# coilcube.net
KiCad netlist of a schematic drawn in EAGLE
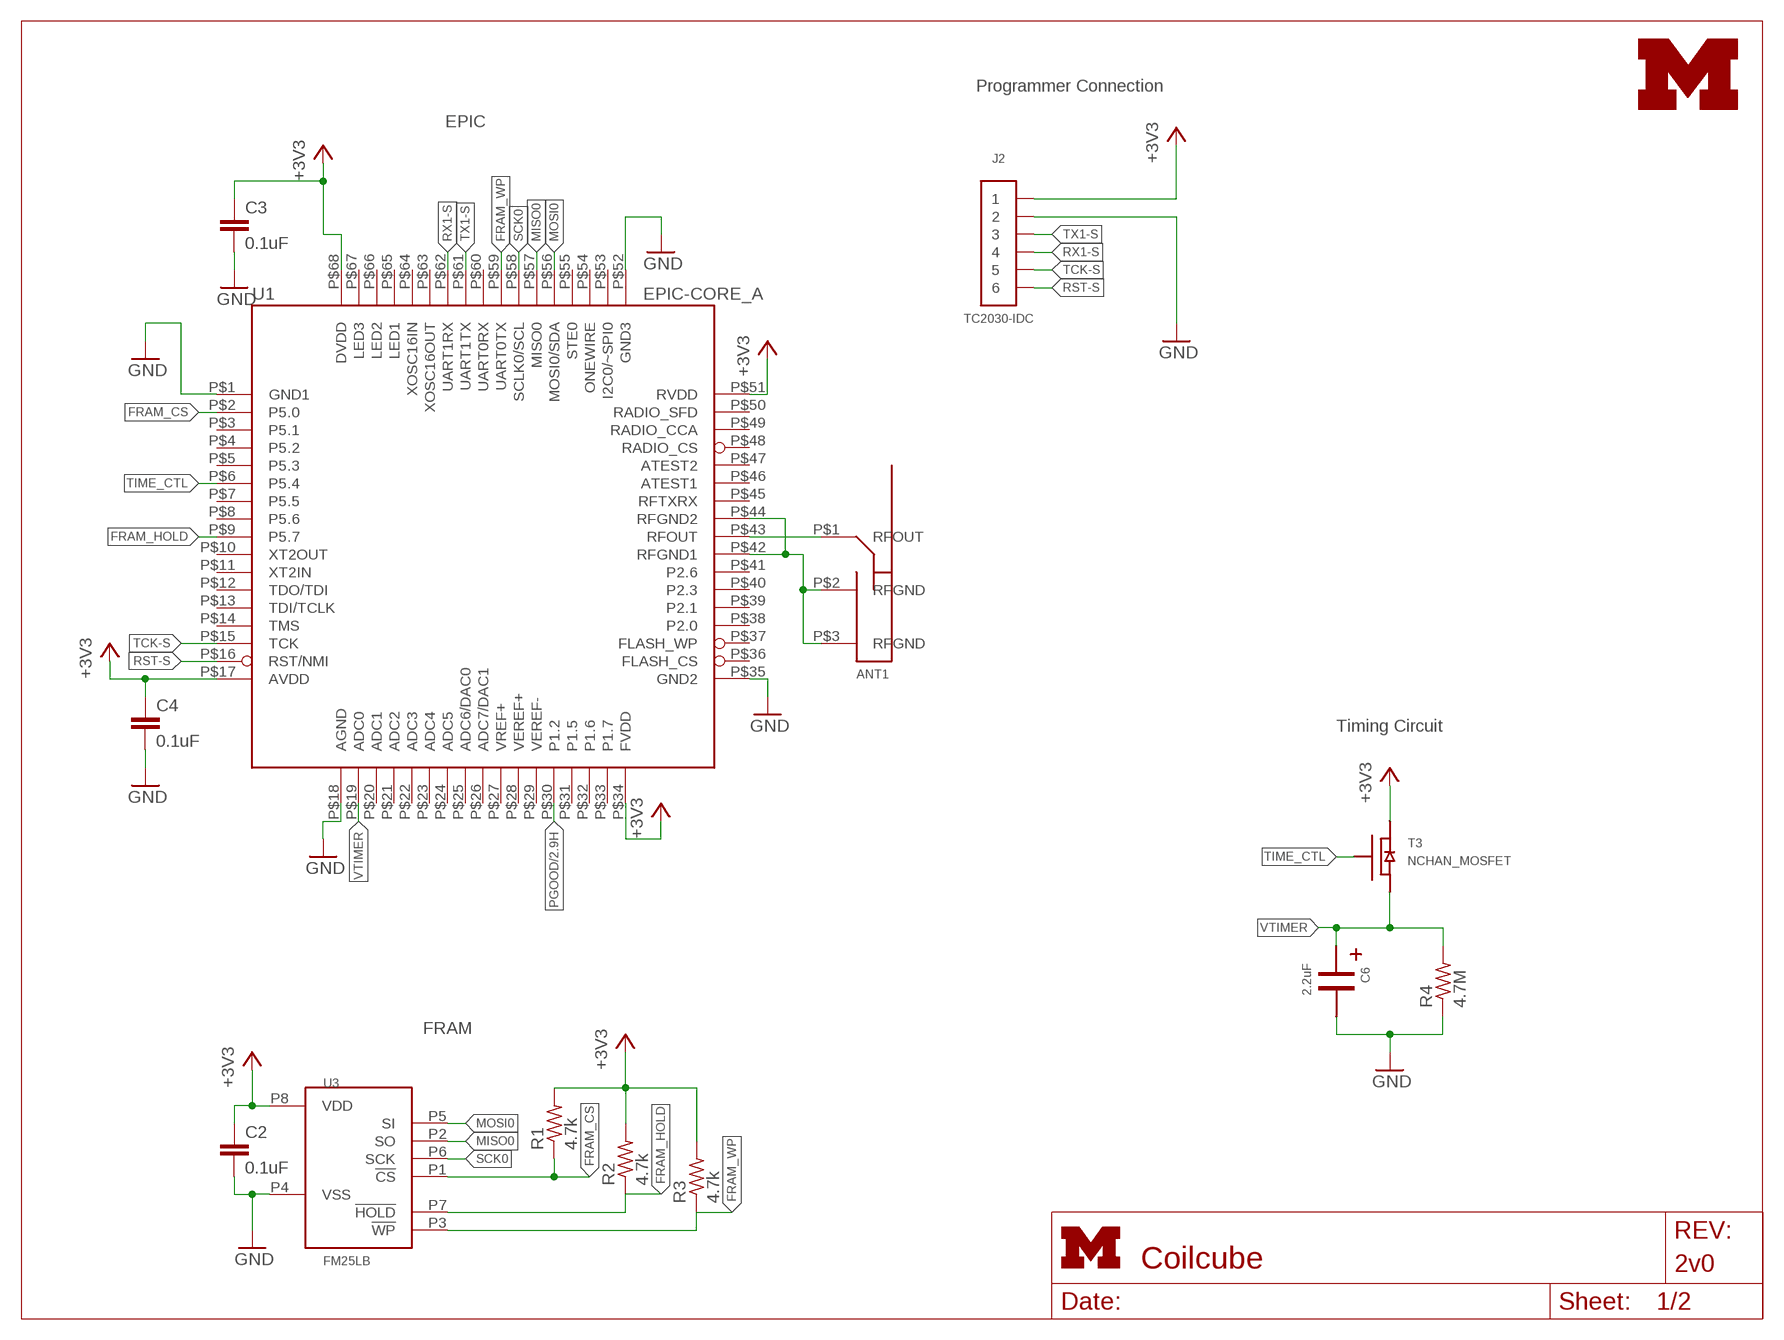
[diagram p0: schematic, sheet 1]
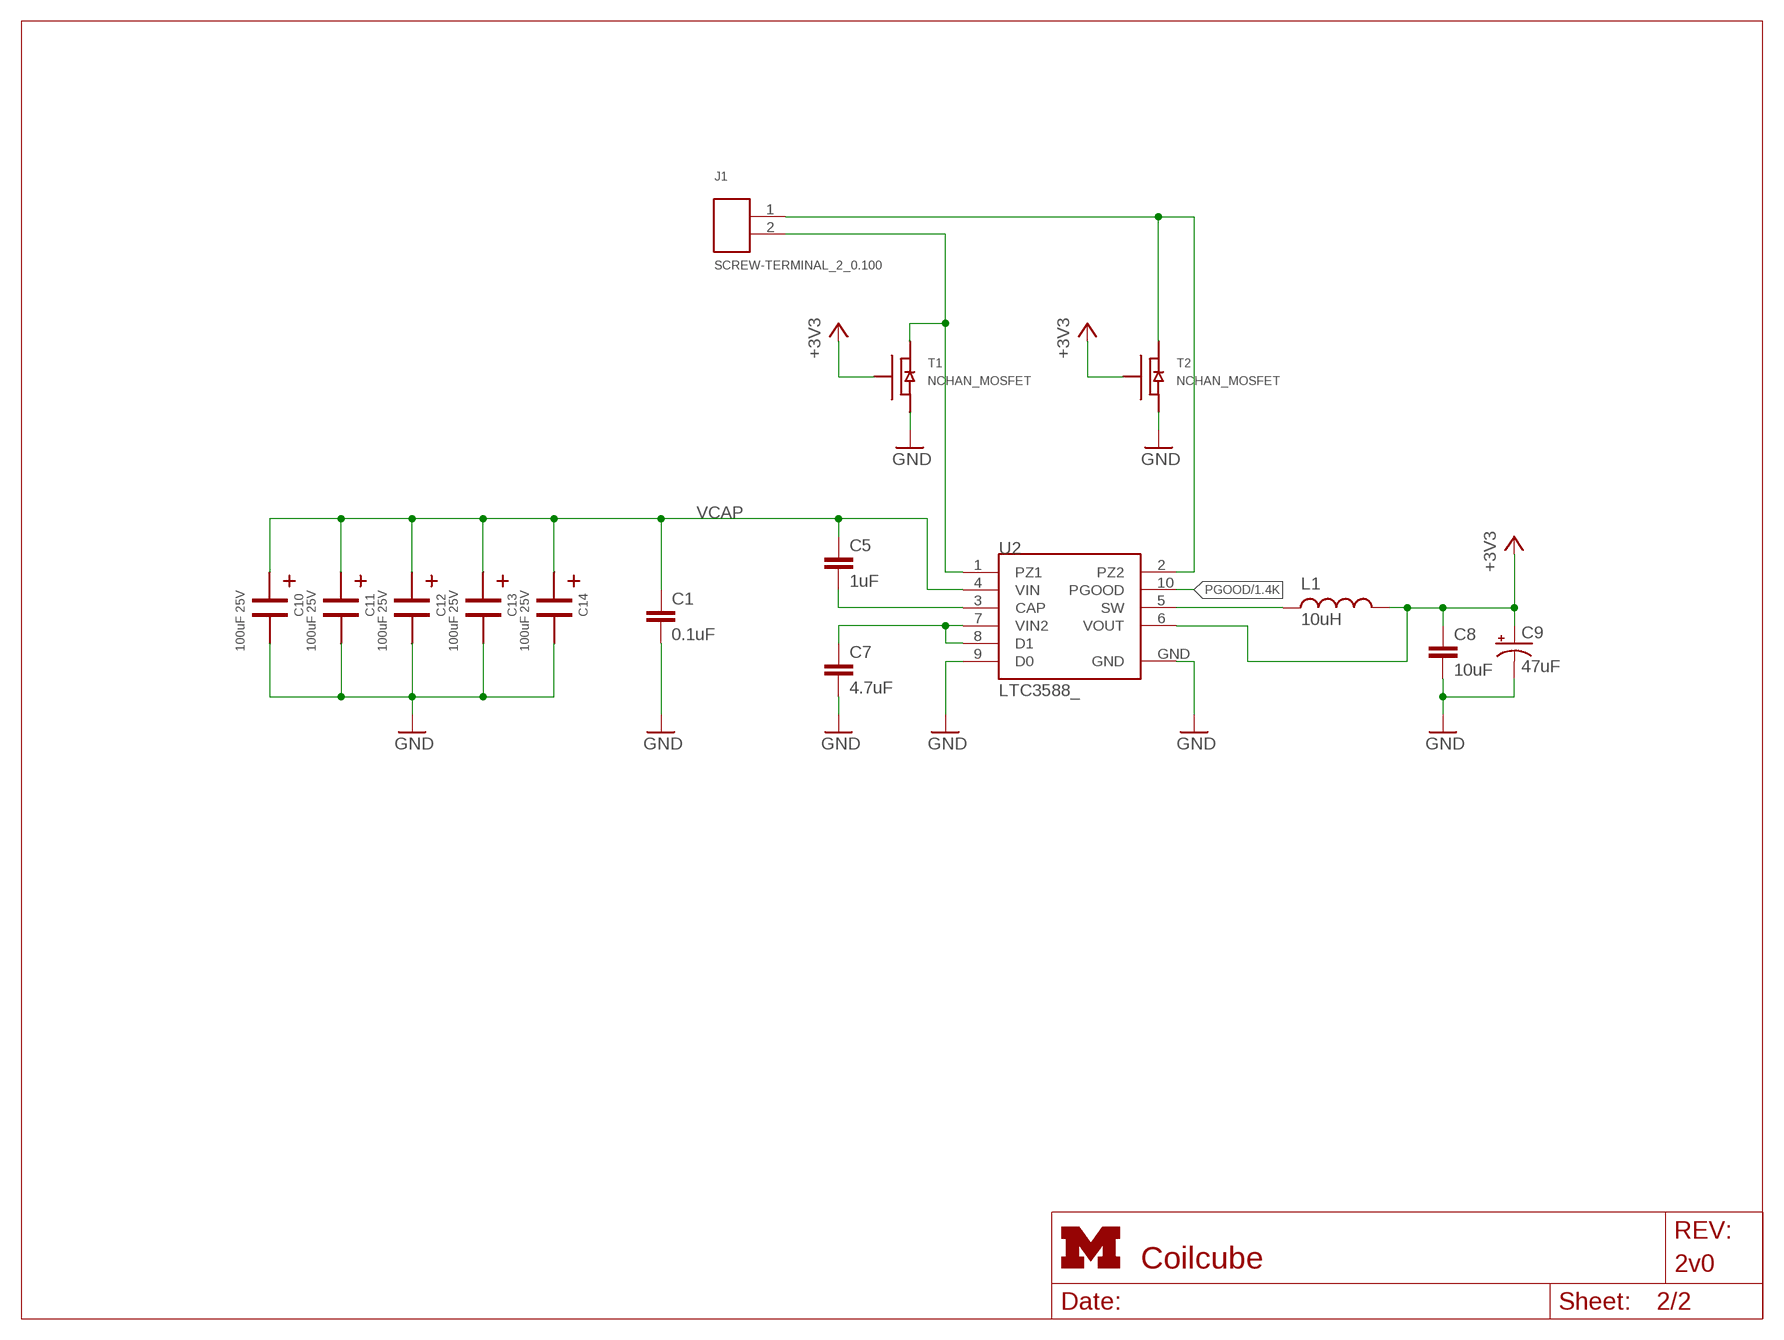
[diagram p1: schematic, sheet 2]

(export (version "E")
  (design (tool "Eeschema 10.0.6"))
  (components
    (comp (ref "ANT1")
      (value "PIFA-2.4GHZ")
      (footprint "eagle-import:PIFA-2.4GHZ")
      (libsource (lib "eagle-import") (part "PIFA-2.4GHZ"))
    )
    (comp (ref "C2")
      (value "0.1uF")
      (footprint "eagle-import:C0603")
      (libsource (lib "eagle-import") (part "C-EUC0603"))
    )
    (comp (ref "C3")
      (value "0.1uF")
      (footprint "eagle-import:C0603")
      (libsource (lib "eagle-import") (part "C-EUC0603"))
    )
    (comp (ref "C4")
      (value "0.1uF")
      (footprint "eagle-import:C0603")
      (libsource (lib "eagle-import") (part "C-EUC0603"))
    )
    (comp (ref "C6")
      (value "2.2uF")
      (footprint "eagle-import:CPOL_EEA_1MM5")
      (libsource (lib "eagle-import") (part "CAP_POLEA1MM5"))
    )
    (comp (ref "J2")
      (value "TC2030-IDC")
      (footprint "eagle-import:TC2030-IDC")
      (libsource (lib "eagle-import") (part "TC2030-IDC"))
    )
    (comp (ref "R1")
      (value "4.7k")
      (footprint "eagle-import:R0603")
      (libsource (lib "eagle-import") (part "R-US_R0603"))
    )
    (comp (ref "R2")
      (value "4.7k")
      (footprint "eagle-import:R0603")
      (libsource (lib "eagle-import") (part "R-US_R0603"))
    )
    (comp (ref "R3")
      (value "4.7k")
      (footprint "eagle-import:R0603")
      (libsource (lib "eagle-import") (part "R-US_R0603"))
    )
    (comp (ref "R4")
      (value "4.7M")
      (footprint "eagle-import:R0805")
      (libsource (lib "eagle-import") (part "R-US_R0805"))
    )
    (comp (ref "T3")
      (value "NCHAN_MOSFET")
      (footprint "eagle-import:NCHAN_MOSFET")
      (libsource (lib "eagle-import") (part "NCHAN_MOSFET"))
    )
    (comp (ref "U$1")
      (value "UMICH_SOLID_MEDIUM")
      (footprint "eagle-import:UMICH_SOLID_200MIL")
      (libsource (lib "eagle-import") (part "UMICH_SOLID_MEDIUM"))
    )
    (comp (ref "U1")
      (value "EPIC-CORE_A")
      (footprint "eagle-import:EPIC-LCC68")
      (libsource (lib "eagle-import") (part "EPIC-CORE_A"))
    )
    (comp (ref "U3")
      (value "FM25LB")
      (footprint "eagle-import:SOIC_8")
      (libsource (lib "eagle-import") (part "FM25LB"))
    )
    (comp (ref "C1")
      (value "0.1uF")
      (footprint "eagle-import:C0603")
      (libsource (lib "eagle-import") (part "C-EUC0603"))
    )
    (comp (ref "C5")
      (value "1uF")
      (footprint "eagle-import:C0603")
      (libsource (lib "eagle-import") (part "C-EUC0603"))
    )
    (comp (ref "C7")
      (value "4.7uF")
      (footprint "eagle-import:C0603")
      (libsource (lib "eagle-import") (part "C-EUC0603"))
    )
    (comp (ref "C8")
      (value "10uF")
      (footprint "eagle-import:C1206")
      (libsource (lib "eagle-import") (part "C-EUC1206"))
    )
    (comp (ref "C9")
      (value "47uF")
      (footprint "eagle-import:EIA3216")
      (libsource (lib "eagle-import") (part "CAP_POL1206"))
    )
    (comp (ref "C10")
      (value "100uF 25V")
      (footprint "eagle-import:2917_CAP_POL")
      (libsource (lib "eagle-import") (part "2917_CAP_POL"))
    )
    (comp (ref "C11")
      (value "100uF 25V")
      (footprint "eagle-import:2917_CAP_POL")
      (libsource (lib "eagle-import") (part "2917_CAP_POL"))
    )
    (comp (ref "C12")
      (value "100uF 25V")
      (footprint "eagle-import:2917_CAP_POL")
      (libsource (lib "eagle-import") (part "2917_CAP_POL"))
    )
    (comp (ref "C13")
      (value "100uF 25V")
      (footprint "eagle-import:2917_CAP_POL")
      (libsource (lib "eagle-import") (part "2917_CAP_POL"))
    )
    (comp (ref "C14")
      (value "100uF 25V")
      (footprint "eagle-import:2917_CAP_POL")
      (libsource (lib "eagle-import") (part "2917_CAP_POL"))
    )
    (comp (ref "J1")
      (value "SCREW-TERMINAL_2_0.100")
      (footprint "eagle-import:CONN_BLOCK_2")
      (libsource (lib "eagle-import") (part "SCREW-TERMINAL_2_0.100"))
    )
    (comp (ref "L1")
      (value "10uH")
      (footprint "eagle-import:1210")
      (libsource (lib "eagle-import") (part "INDUCTOR1210"))
    )
    (comp (ref "T1")
      (value "NCHAN_MOSFET")
      (footprint "eagle-import:NCHAN_MOSFET")
      (libsource (lib "eagle-import") (part "NCHAN_MOSFET"))
    )
    (comp (ref "T2")
      (value "NCHAN_MOSFET")
      (footprint "eagle-import:NCHAN_MOSFET")
      (libsource (lib "eagle-import") (part "NCHAN_MOSFET"))
    )
    (comp (ref "U2")
      (value "LTC3588_")
      (footprint "eagle-import:MSOP-10-GNDPAD")
      (libsource (lib "eagle-import") (part "LTC3588_"))
    )
  )
  (nets
    (net (code "1") (name "+3V3") (class "Default")
      (node (ref "C2") (pin "1") (pinfunction "1_1") (pintype "passive"))
      (node (ref "C3") (pin "1") (pinfunction "1_1") (pintype "passive"))
      (node (ref "C4") (pin "1") (pinfunction "1_1") (pintype "passive"))
      (node (ref "C8") (pin "1") (pinfunction "1_1") (pintype "passive"))
      (node (ref "C9") (pin "A") (pinfunction "+_A") (pintype "passive"))
      (node (ref "J2") (pin "1") (pinfunction "1_1") (pintype "bidirectional"))
      (node (ref "L1") (pin "2") (pinfunction "2_2") (pintype "passive"))
      (node (ref "R1") (pin "2") (pinfunction "2_2") (pintype "passive"))
      (node (ref "R2") (pin "2") (pinfunction "2_2") (pintype "passive"))
      (node (ref "R3") (pin "2") (pinfunction "2_2") (pintype "passive"))
      (node (ref "T1") (pin "G") (pinfunction "G_G") (pintype "bidirectional"))
      (node (ref "T2") (pin "G") (pinfunction "G_G") (pintype "bidirectional"))
      (node (ref "T3") (pin "D") (pinfunction "D_D") (pintype "bidirectional"))
      (node (ref "U1") (pin "P$17") (pinfunction "AVDD_P$17") (pintype "bidirectional"))
      (node (ref "U1") (pin "P$34") (pinfunction "FVDD_P$34") (pintype "bidirectional"))
      (node (ref "U1") (pin "P$51") (pinfunction "RVDD_P$51") (pintype "bidirectional"))
      (node (ref "U1") (pin "P$68") (pinfunction "DVDD_P$68") (pintype "bidirectional"))
      (node (ref "U2") (pin "6") (pinfunction "VOUT_6") (pintype "bidirectional"))
      (node (ref "U3") (pin "P8") (pinfunction "VDD_P8") (pintype "bidirectional"))
    )
    (net (code "2") (name "FRAM_CS") (class "Default")
      (node (ref "R1") (pin "1") (pinfunction "1_1") (pintype "passive"))
      (node (ref "U1") (pin "P$2") (pinfunction "P5.0_P$2") (pintype "bidirectional"))
      (node (ref "U3") (pin "P1") (pinfunction "~{CS}_P1") (pintype "bidirectional"))
    )
    (net (code "3") (name "FRAM_HOLD") (class "Default")
      (node (ref "R2") (pin "1") (pinfunction "1_1") (pintype "passive"))
      (node (ref "U1") (pin "P$9") (pinfunction "P5.7_P$9") (pintype "bidirectional"))
      (node (ref "U3") (pin "P7") (pinfunction "~{HOLD}_P7") (pintype "bidirectional"))
    )
    (net (code "4") (name "FRAM_WP") (class "Default")
      (node (ref "R3") (pin "1") (pinfunction "1_1") (pintype "passive"))
      (node (ref "U1") (pin "P$59") (pinfunction "UART0TX_P$59") (pintype "bidirectional"))
      (node (ref "U3") (pin "P3") (pinfunction "~{WP}_P3") (pintype "bidirectional"))
    )
    (net (code "5") (name "GND") (class "Default")
      (node (ref "C1") (pin "2") (pinfunction "2_2") (pintype "passive"))
      (node (ref "C10") (pin "-") (pinfunction "-_-") (pintype "bidirectional"))
      (node (ref "C11") (pin "-") (pinfunction "-_-") (pintype "bidirectional"))
      (node (ref "C12") (pin "-") (pinfunction "-_-") (pintype "bidirectional"))
      (node (ref "C13") (pin "-") (pinfunction "-_-") (pintype "bidirectional"))
      (node (ref "C14") (pin "-") (pinfunction "-_-") (pintype "bidirectional"))
      (node (ref "C2") (pin "2") (pinfunction "2_2") (pintype "passive"))
      (node (ref "C3") (pin "2") (pinfunction "2_2") (pintype "passive"))
      (node (ref "C4") (pin "2") (pinfunction "2_2") (pintype "passive"))
      (node (ref "C6") (pin "-") (pinfunction "-_-") (pintype "bidirectional"))
      (node (ref "C7") (pin "2") (pinfunction "2_2") (pintype "passive"))
      (node (ref "C8") (pin "2") (pinfunction "2_2") (pintype "passive"))
      (node (ref "C9") (pin "C") (pinfunction "-_C") (pintype "passive"))
      (node (ref "J2") (pin "2") (pinfunction "2_2") (pintype "bidirectional"))
      (node (ref "R4") (pin "1") (pinfunction "1_1") (pintype "passive"))
      (node (ref "T1") (pin "S") (pinfunction "S_S") (pintype "bidirectional"))
      (node (ref "T2") (pin "S") (pinfunction "S_S") (pintype "bidirectional"))
      (node (ref "U1") (pin "P$1") (pinfunction "GND1_P$1") (pintype "bidirectional"))
      (node (ref "U1") (pin "P$18") (pinfunction "AGND_P$18") (pintype "bidirectional"))
      (node (ref "U1") (pin "P$35") (pinfunction "GND2_P$35") (pintype "bidirectional"))
      (node (ref "U1") (pin "P$52") (pinfunction "GND3_P$52") (pintype "bidirectional"))
      (node (ref "U2") (pin "9") (pinfunction "D0_9") (pintype "bidirectional"))
      (node (ref "U2") (pin "GND") (pinfunction "GND_GND") (pintype "bidirectional"))
      (node (ref "U3") (pin "P4") (pinfunction "VSS_P4") (pintype "bidirectional"))
    )
    (net (code "6") (name "MISO0") (class "Default")
      (node (ref "U1") (pin "P$57") (pinfunction "MISO0_P$57") (pintype "bidirectional"))
      (node (ref "U3") (pin "P2") (pinfunction "SO_P2") (pintype "bidirectional"))
    )
    (net (code "7") (name "MOSI0") (class "Default")
      (node (ref "U1") (pin "P$56") (pinfunction "MOSI0/SDA_P$56") (pintype "bidirectional"))
      (node (ref "U3") (pin "P5") (pinfunction "SI_P5") (pintype "bidirectional"))
    )
    (net (code "8") (name "Net-(ANT1-RFOUT)") (class "Default")
      (node (ref "ANT1") (pin "P$1") (pinfunction "RFOUT_P$1") (pintype "bidirectional"))
      (node (ref "U1") (pin "P$43") (pinfunction "RFOUT_P$43") (pintype "bidirectional"))
    )
    (net (code "9") (name "Net-(U1-RFGND1)") (class "Default")
      (node (ref "ANT1") (pin "P$2") (pinfunction "RFGND_P$2") (pintype "bidirectional"))
      (node (ref "ANT1") (pin "P$3") (pinfunction "RFGND_P$3") (pintype "bidirectional"))
      (node (ref "U1") (pin "P$42") (pinfunction "RFGND1_P$42") (pintype "bidirectional"))
      (node (ref "U1") (pin "P$44") (pinfunction "RFGND2_P$44") (pintype "bidirectional"))
    )
    (net (code "10") (name "Net-(U2-CAP)") (class "Default")
      (node (ref "C5") (pin "2") (pinfunction "2_2") (pintype "passive"))
      (node (ref "U2") (pin "3") (pinfunction "CAP_3") (pintype "bidirectional"))
    )
    (net (code "11") (name "Net-(U2-D1)") (class "Default")
      (node (ref "C7") (pin "1") (pinfunction "1_1") (pintype "passive"))
      (node (ref "U2") (pin "7") (pinfunction "VIN2_7") (pintype "bidirectional"))
      (node (ref "U2") (pin "8") (pinfunction "D1_8") (pintype "bidirectional"))
    )
    (net (code "12") (name "Net-(U2-PZ1)") (class "Default")
      (node (ref "J1") (pin "2") (pinfunction "2_2") (pintype "bidirectional"))
      (node (ref "T1") (pin "D") (pinfunction "D_D") (pintype "bidirectional"))
      (node (ref "U2") (pin "1") (pinfunction "PZ1_1") (pintype "bidirectional"))
    )
    (net (code "13") (name "Net-(U2-PZ2)") (class "Default")
      (node (ref "J1") (pin "1") (pinfunction "1_1") (pintype "bidirectional"))
      (node (ref "T2") (pin "D") (pinfunction "D_D") (pintype "bidirectional"))
      (node (ref "U2") (pin "2") (pinfunction "PZ2_2") (pintype "bidirectional"))
    )
    (net (code "14") (name "Net-(U2-SW)") (class "Default")
      (node (ref "L1") (pin "1") (pinfunction "1_1") (pintype "passive"))
      (node (ref "U2") (pin "5") (pinfunction "SW_5") (pintype "bidirectional"))
    )
    (net (code "15") (name "PGOOD") (class "Default")
      (node (ref "U1") (pin "P$30") (pinfunction "P1.2_P$30") (pintype "bidirectional"))
      (node (ref "U2") (pin "10") (pinfunction "PGOOD_10") (pintype "bidirectional"))
    )
    (net (code "16") (name "RST-S") (class "Default")
      (node (ref "J2") (pin "6") (pinfunction "6_6") (pintype "bidirectional"))
      (node (ref "U1") (pin "P$16") (pinfunction "RST/NMI_P$16") (pintype "bidirectional"))
    )
    (net (code "17") (name "RX1-S") (class "Default")
      (node (ref "J2") (pin "4") (pinfunction "4_4") (pintype "bidirectional"))
      (node (ref "U1") (pin "P$62") (pinfunction "UART1RX_P$62") (pintype "bidirectional"))
    )
    (net (code "18") (name "SCK0") (class "Default")
      (node (ref "U1") (pin "P$58") (pinfunction "SCLK0/SCL_P$58") (pintype "bidirectional"))
      (node (ref "U3") (pin "P6") (pinfunction "SCK_P6") (pintype "bidirectional"))
    )
    (net (code "19") (name "TCK-S") (class "Default")
      (node (ref "J2") (pin "5") (pinfunction "5_5") (pintype "bidirectional"))
      (node (ref "U1") (pin "P$15") (pinfunction "TCK_P$15") (pintype "bidirectional"))
    )
    (net (code "20") (name "TIME_CTL") (class "Default")
      (node (ref "T3") (pin "G") (pinfunction "G_G") (pintype "bidirectional"))
      (node (ref "U1") (pin "P$6") (pinfunction "P5.4_P$6") (pintype "bidirectional"))
    )
    (net (code "21") (name "TX1-S") (class "Default")
      (node (ref "J2") (pin "3") (pinfunction "3_3") (pintype "bidirectional"))
      (node (ref "U1") (pin "P$61") (pinfunction "UART1TX_P$61") (pintype "bidirectional"))
    )
    (net (code "22") (name "VCAP") (class "Default")
      (node (ref "C1") (pin "1") (pinfunction "1_1") (pintype "passive"))
      (node (ref "C10") (pin "+") (pinfunction "+_+") (pintype "bidirectional"))
      (node (ref "C11") (pin "+") (pinfunction "+_+") (pintype "bidirectional"))
      (node (ref "C12") (pin "+") (pinfunction "+_+") (pintype "bidirectional"))
      (node (ref "C13") (pin "+") (pinfunction "+_+") (pintype "bidirectional"))
      (node (ref "C14") (pin "+") (pinfunction "+_+") (pintype "bidirectional"))
      (node (ref "C5") (pin "1") (pinfunction "1_1") (pintype "passive"))
      (node (ref "U2") (pin "4") (pinfunction "VIN_4") (pintype "bidirectional"))
    )
    (net (code "23") (name "VTIMER") (class "Default")
      (node (ref "C6") (pin "+") (pinfunction "+_+") (pintype "bidirectional"))
      (node (ref "R4") (pin "2") (pinfunction "2_2") (pintype "passive"))
      (node (ref "T3") (pin "S") (pinfunction "S_S") (pintype "bidirectional"))
      (node (ref "U1") (pin "P$19") (pinfunction "ADC0_P$19") (pintype "bidirectional"))
    )
    (net (code "24") (name "unconnected-(U1-ADC1-PadP$20)") (class "Default")
      (node (ref "U1") (pin "P$20") (pinfunction "ADC1_P$20") (pintype "bidirectional"))
    )
    (net (code "25") (name "unconnected-(U1-ADC2-PadP$21)") (class "Default")
      (node (ref "U1") (pin "P$21") (pinfunction "ADC2_P$21") (pintype "bidirectional"))
    )
    (net (code "26") (name "unconnected-(U1-ADC3-PadP$22)") (class "Default")
      (node (ref "U1") (pin "P$22") (pinfunction "ADC3_P$22") (pintype "bidirectional"))
    )
    (net (code "27") (name "unconnected-(U1-ADC4-PadP$23)") (class "Default")
      (node (ref "U1") (pin "P$23") (pinfunction "ADC4_P$23") (pintype "bidirectional"))
    )
    (net (code "28") (name "unconnected-(U1-ADC5-PadP$24)") (class "Default")
      (node (ref "U1") (pin "P$24") (pinfunction "ADC5_P$24") (pintype "bidirectional"))
    )
    (net (code "29") (name "unconnected-(U1-ADC6{slash}DAC0-PadP$25)") (class "Default")
      (node (ref "U1") (pin "P$25") (pinfunction "ADC6/DAC0_P$25") (pintype "bidirectional"))
    )
    (net (code "30") (name "unconnected-(U1-ADC7{slash}DAC1-PadP$26)") (class "Default")
      (node (ref "U1") (pin "P$26") (pinfunction "ADC7/DAC1_P$26") (pintype "bidirectional"))
    )
    (net (code "31") (name "unconnected-(U1-ATEST1-PadP$46)") (class "Default")
      (node (ref "U1") (pin "P$46") (pinfunction "ATEST1_P$46") (pintype "bidirectional"))
    )
    (net (code "32") (name "unconnected-(U1-ATEST2-PadP$47)") (class "Default")
      (node (ref "U1") (pin "P$47") (pinfunction "ATEST2_P$47") (pintype "bidirectional"))
    )
    (net (code "33") (name "unconnected-(U1-FLASH_CS-PadP$36)") (class "Default")
      (node (ref "U1") (pin "P$36") (pinfunction "FLASH_CS_P$36") (pintype "bidirectional"))
    )
    (net (code "34") (name "unconnected-(U1-FLASH_WP-PadP$37)") (class "Default")
      (node (ref "U1") (pin "P$37") (pinfunction "FLASH_WP_P$37") (pintype "bidirectional"))
    )
    (net (code "35") (name "unconnected-(U1-I2C0{slash}~{SPI0}-PadP$53)") (class "Default")
      (node (ref "U1") (pin "P$53") (pinfunction "I2C0/~{SPI0}_P$53") (pintype "bidirectional"))
    )
    (net (code "36") (name "unconnected-(U1-LED1-PadP$65)") (class "Default")
      (node (ref "U1") (pin "P$65") (pinfunction "LED1_P$65") (pintype "bidirectional"))
    )
    (net (code "37") (name "unconnected-(U1-LED2-PadP$66)") (class "Default")
      (node (ref "U1") (pin "P$66") (pinfunction "LED2_P$66") (pintype "bidirectional"))
    )
    (net (code "38") (name "unconnected-(U1-LED3-PadP$67)") (class "Default")
      (node (ref "U1") (pin "P$67") (pinfunction "LED3_P$67") (pintype "bidirectional"))
    )
    (net (code "39") (name "unconnected-(U1-ONEWIRE-PadP$54)") (class "Default")
      (node (ref "U1") (pin "P$54") (pinfunction "ONEWIRE_P$54") (pintype "bidirectional"))
    )
    (net (code "40") (name "unconnected-(U1-P1.5-PadP$31)") (class "Default")
      (node (ref "U1") (pin "P$31") (pinfunction "P1.5_P$31") (pintype "bidirectional"))
    )
    (net (code "41") (name "unconnected-(U1-P1.6-PadP$32)") (class "Default")
      (node (ref "U1") (pin "P$32") (pinfunction "P1.6_P$32") (pintype "bidirectional"))
    )
    (net (code "42") (name "unconnected-(U1-P1.7-PadP$33)") (class "Default")
      (node (ref "U1") (pin "P$33") (pinfunction "P1.7_P$33") (pintype "bidirectional"))
    )
    (net (code "43") (name "unconnected-(U1-P2.0-PadP$38)") (class "Default")
      (node (ref "U1") (pin "P$38") (pinfunction "P2.0_P$38") (pintype "bidirectional"))
    )
    (net (code "44") (name "unconnected-(U1-P2.1-PadP$39)") (class "Default")
      (node (ref "U1") (pin "P$39") (pinfunction "P2.1_P$39") (pintype "bidirectional"))
    )
    (net (code "45") (name "unconnected-(U1-P2.3-PadP$40)") (class "Default")
      (node (ref "U1") (pin "P$40") (pinfunction "P2.3_P$40") (pintype "bidirectional"))
    )
    (net (code "46") (name "unconnected-(U1-P2.6-PadP$41)") (class "Default")
      (node (ref "U1") (pin "P$41") (pinfunction "P2.6_P$41") (pintype "bidirectional"))
    )
    (net (code "47") (name "unconnected-(U1-P5.1-PadP$3)") (class "Default")
      (node (ref "U1") (pin "P$3") (pinfunction "P5.1_P$3") (pintype "bidirectional"))
    )
    (net (code "48") (name "unconnected-(U1-P5.2-PadP$4)") (class "Default")
      (node (ref "U1") (pin "P$4") (pinfunction "P5.2_P$4") (pintype "bidirectional"))
    )
    (net (code "49") (name "unconnected-(U1-P5.3-PadP$5)") (class "Default")
      (node (ref "U1") (pin "P$5") (pinfunction "P5.3_P$5") (pintype "bidirectional"))
    )
    (net (code "50") (name "unconnected-(U1-P5.5-PadP$7)") (class "Default")
      (node (ref "U1") (pin "P$7") (pinfunction "P5.5_P$7") (pintype "bidirectional"))
    )
    (net (code "51") (name "unconnected-(U1-P5.6-PadP$8)") (class "Default")
      (node (ref "U1") (pin "P$8") (pinfunction "P5.6_P$8") (pintype "bidirectional"))
    )
    (net (code "52") (name "unconnected-(U1-RADIO_CCA-PadP$49)") (class "Default")
      (node (ref "U1") (pin "P$49") (pinfunction "RADIO_CCA_P$49") (pintype "bidirectional"))
    )
    (net (code "53") (name "unconnected-(U1-RADIO_CS-PadP$48)") (class "Default")
      (node (ref "U1") (pin "P$48") (pinfunction "RADIO_CS_P$48") (pintype "bidirectional"))
    )
    (net (code "54") (name "unconnected-(U1-RADIO_SFD-PadP$50)") (class "Default")
      (node (ref "U1") (pin "P$50") (pinfunction "RADIO_SFD_P$50") (pintype "bidirectional"))
    )
    (net (code "55") (name "unconnected-(U1-RFTXRX-PadP$45)") (class "Default")
      (node (ref "U1") (pin "P$45") (pinfunction "RFTXRX_P$45") (pintype "bidirectional"))
    )
    (net (code "56") (name "unconnected-(U1-STE0-PadP$55)") (class "Default")
      (node (ref "U1") (pin "P$55") (pinfunction "STE0_P$55") (pintype "bidirectional"))
    )
    (net (code "57") (name "unconnected-(U1-TDI{slash}TCLK-PadP$13)") (class "Default")
      (node (ref "U1") (pin "P$13") (pinfunction "TDI/TCLK_P$13") (pintype "bidirectional"))
    )
    (net (code "58") (name "unconnected-(U1-TDO{slash}TDI-PadP$12)") (class "Default")
      (node (ref "U1") (pin "P$12") (pinfunction "TDO/TDI_P$12") (pintype "bidirectional"))
    )
    (net (code "59") (name "unconnected-(U1-TMS-PadP$14)") (class "Default")
      (node (ref "U1") (pin "P$14") (pinfunction "TMS_P$14") (pintype "bidirectional"))
    )
    (net (code "60") (name "unconnected-(U1-UART0RX-PadP$60)") (class "Default")
      (node (ref "U1") (pin "P$60") (pinfunction "UART0RX_P$60") (pintype "bidirectional"))
    )
    (net (code "61") (name "unconnected-(U1-VEREF+-PadP$28)") (class "Default")
      (node (ref "U1") (pin "P$28") (pinfunction "VEREF+_P$28") (pintype "bidirectional"))
    )
    (net (code "62") (name "unconnected-(U1-VEREF--PadP$29)") (class "Default")
      (node (ref "U1") (pin "P$29") (pinfunction "VEREF-_P$29") (pintype "bidirectional"))
    )
    (net (code "63") (name "unconnected-(U1-VREF+-PadP$27)") (class "Default")
      (node (ref "U1") (pin "P$27") (pinfunction "VREF+_P$27") (pintype "bidirectional"))
    )
    (net (code "64") (name "unconnected-(U1-XOSC16IN-PadP$64)") (class "Default")
      (node (ref "U1") (pin "P$64") (pinfunction "XOSC16IN_P$64") (pintype "bidirectional"))
    )
    (net (code "65") (name "unconnected-(U1-XOSC16OUT-PadP$63)") (class "Default")
      (node (ref "U1") (pin "P$63") (pinfunction "XOSC16OUT_P$63") (pintype "bidirectional"))
    )
    (net (code "66") (name "unconnected-(U1-XT2IN-PadP$11)") (class "Default")
      (node (ref "U1") (pin "P$11") (pinfunction "XT2IN_P$11") (pintype "bidirectional"))
    )
    (net (code "67") (name "unconnected-(U1-XT2OUT-PadP$10)") (class "Default")
      (node (ref "U1") (pin "P$10") (pinfunction "XT2OUT_P$10") (pintype "bidirectional"))
    )
  )
)
